# SCH_chris-dual-hd-connector-v3_2021-12-0.net
KiCad netlist of a schematic drawn in EasyEDA
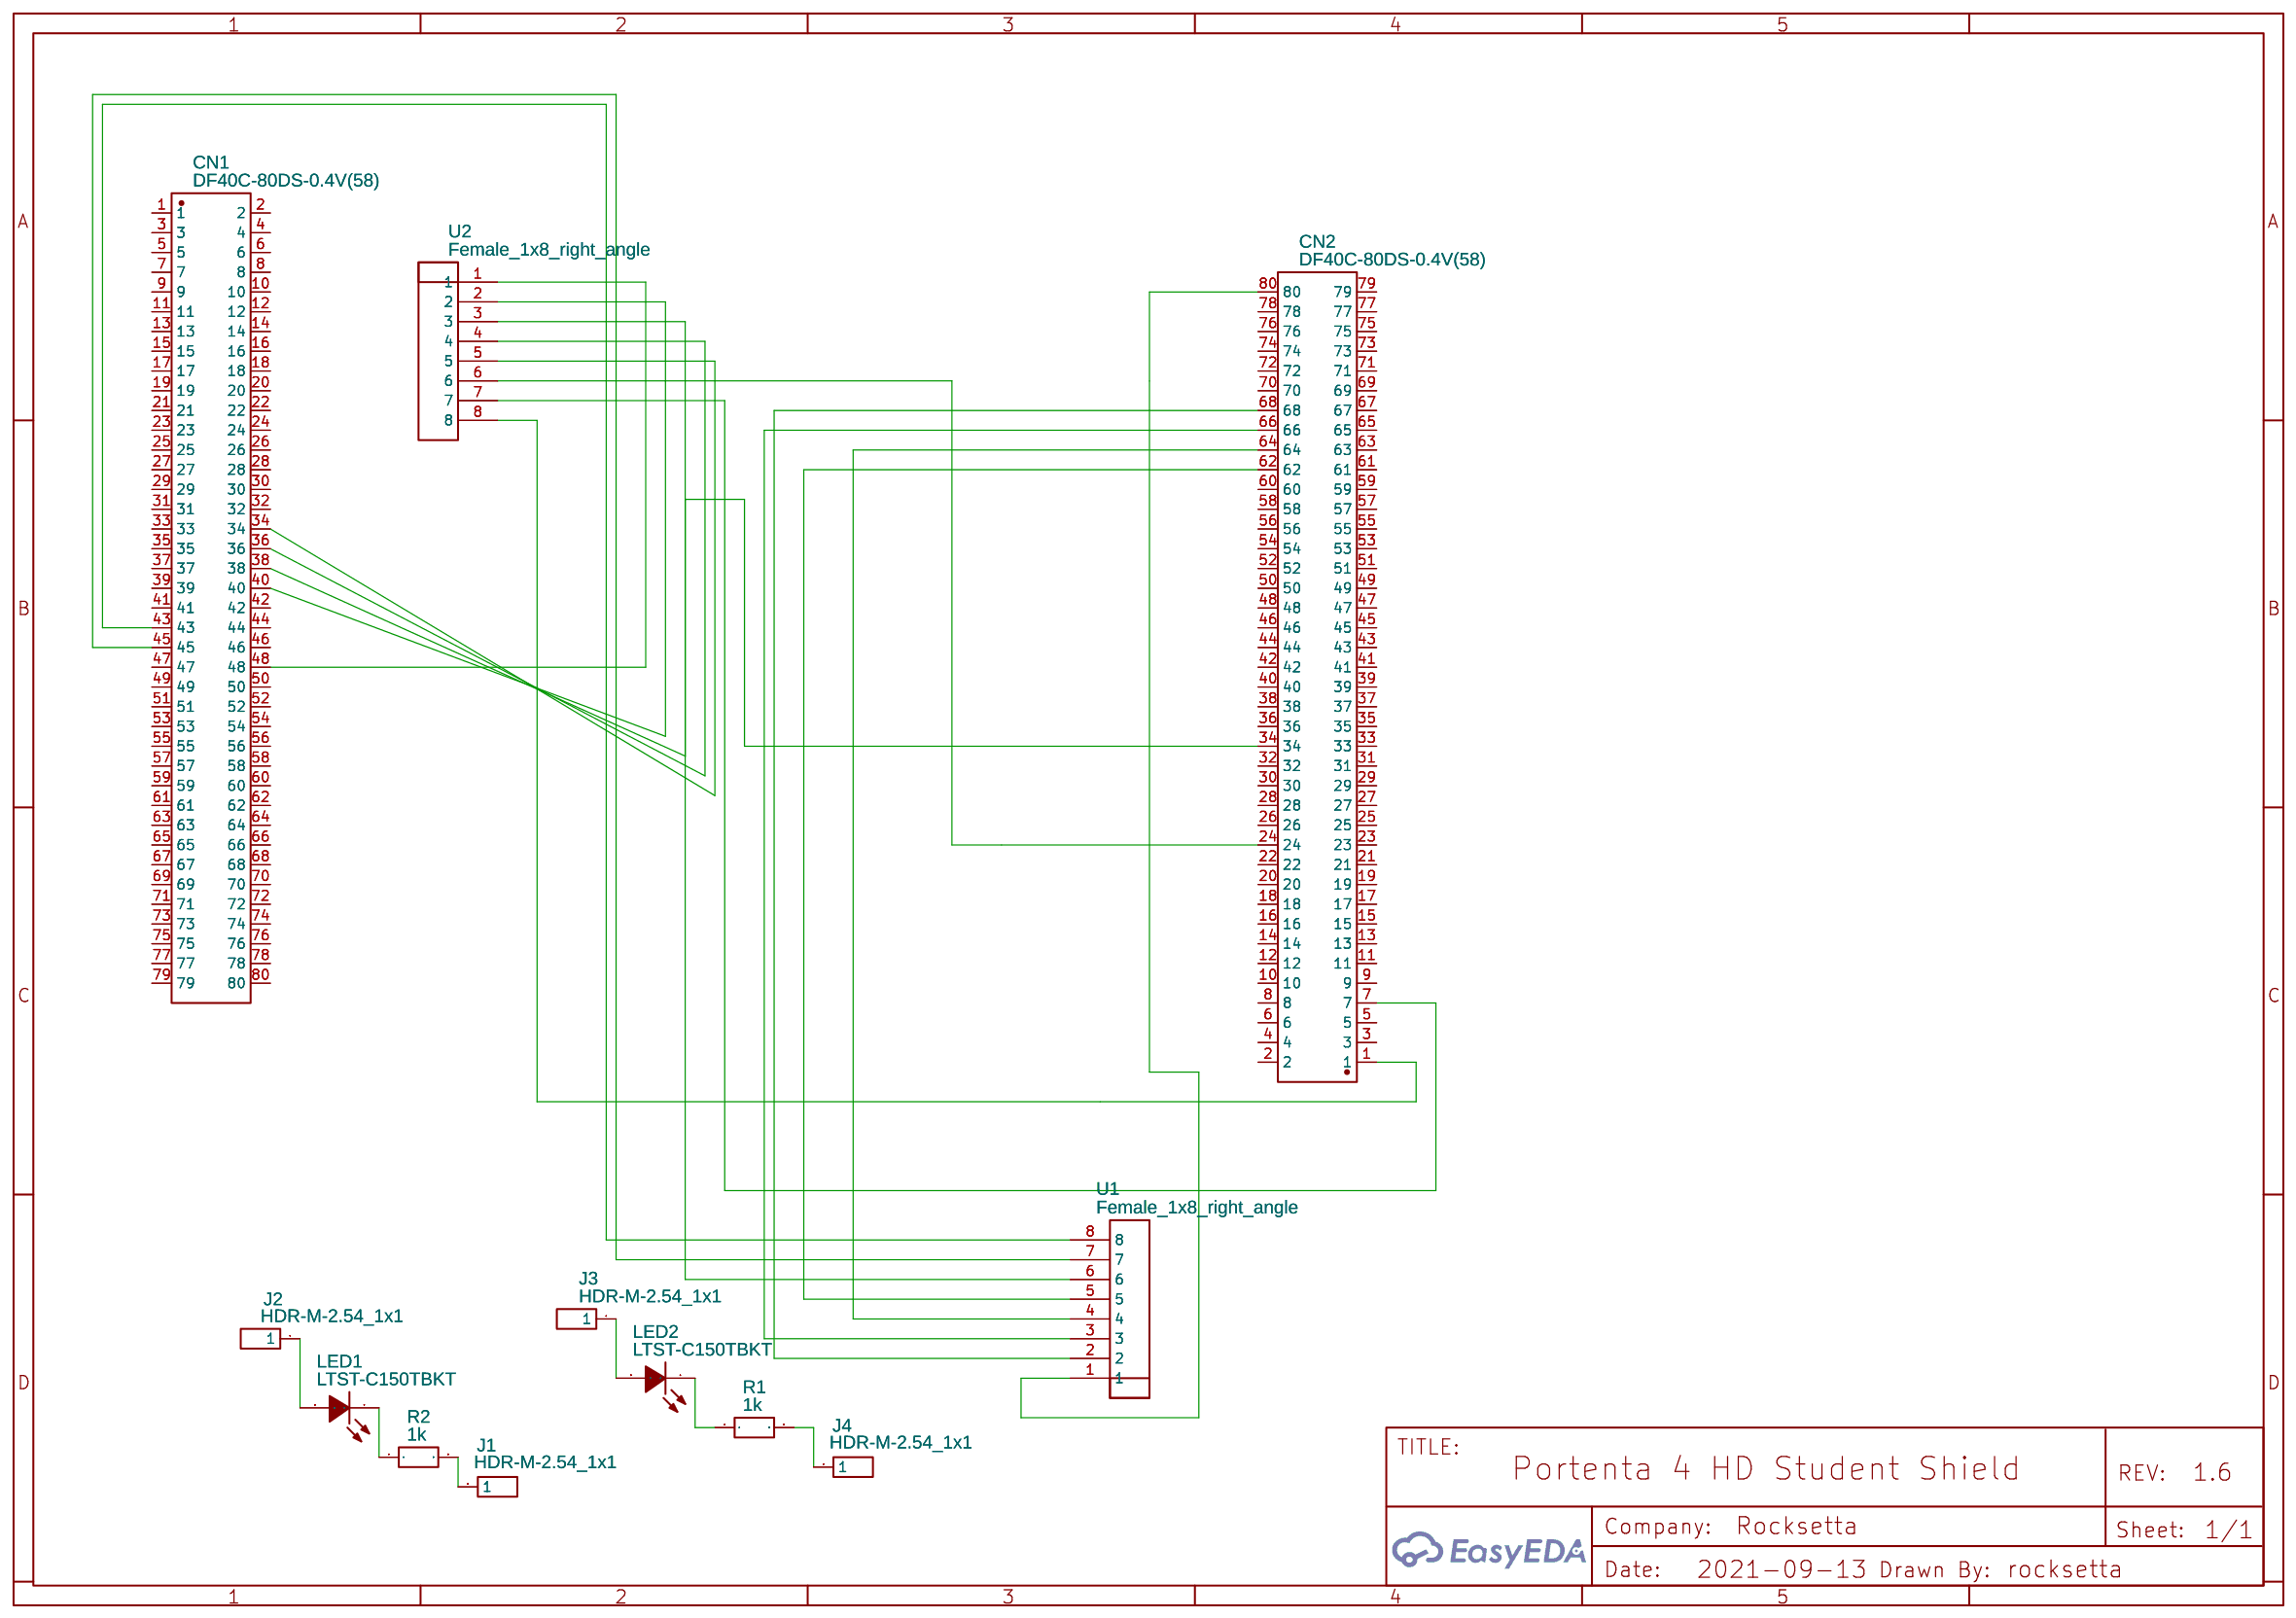
[diagram p0: schematic sheet]

(export (version "E")
  (design (tool "Eeschema 10.0.6"))
  (components
    (comp (ref "CN1")
      (value "DF40C-80DS-0.4V(58)")
      (fields (field (name "BOM_Supplier Part") "C597941"))
      (libsource (lib "") (part "DF40C-80DS-0.4V(58)_1"))
    )
    (comp (ref "CN2")
      (value "DF40C-80DS-0.4V(58)")
      (fields (field (name "BOM_Supplier Part") "C597941"))
      (libsource (lib "") (part "DF40C-80DS-0.4V(58)"))
    )
    (comp (ref "J1")
      (value "HDR-M-2.54_1x1")
      (fields (field (name "BOM_Supplier Part") "C81276"))
      (libsource (lib "") (part "HDR-M-2.54_1x1_1"))
    )
    (comp (ref "J2")
      (value "HDR-M-2.54_1x1")
      (fields (field (name "BOM_Supplier Part") "C81276"))
      (libsource (lib "") (part "HDR-M-2.54_1x1"))
    )
    (comp (ref "J3")
      (value "HDR-M-2.54_1x1")
      (fields (field (name "BOM_Supplier Part") "C81276"))
      (libsource (lib "") (part "HDR-M-2.54_1x1"))
    )
    (comp (ref "J4")
      (value "HDR-M-2.54_1x1")
      (fields (field (name "BOM_Supplier Part") "C81276"))
      (libsource (lib "") (part "HDR-M-2.54_1x1_1"))
    )
    (comp (ref "LED1")
      (value "LTST-C150TBKT")
      (fields (field (name "BOM_Supplier Part") "C125088"))
      (libsource (lib "") (part "LTST-C150TBKT"))
    )
    (comp (ref "LED2")
      (value "LTST-C150TBKT")
      (fields (field (name "BOM_Supplier Part") "C125088"))
      (libsource (lib "") (part "LTST-C150TBKT"))
    )
    (comp (ref "R1") (value "1k") (libsource (lib "") (part "R_0805_EU")))
    (comp (ref "R2") (value "1k") (libsource (lib "") (part "R_0805_EU")))
    (comp (ref "U1")
      (value "Female_1x8_right_angle")
      (fields
        (field (name "BOM_Manufacturer Part") "PPPC081LGBN-RC")
        (field (name "BOM_Supplier Part") "S5483-ND")
      )
      (libsource (lib "") (part "Female_1x8_right_angle"))
    )
    (comp (ref "U2")
      (value "Female_1x8_right_angle")
      (fields
        (field (name "BOM_Manufacturer Part") "PPPC081LGBN-RC")
        (field (name "BOM_Supplier Part") "S5483-ND")
      )
      (libsource (lib "") (part "Female_1x8_right_angle_1"))
    )
  )
  (nets
    (net (code "1") (name "Net-(CN1-Pad34)") (class "Default")
      (node (ref "CN1") (pin "34") (pinfunction "34_34") (pintype "unspecified"))
      (node (ref "U2") (pin "5") (pinfunction "5_5") (pintype "unspecified"))
    )
    (net (code "2") (name "Net-(CN1-Pad36)") (class "Default")
      (node (ref "CN1") (pin "36") (pinfunction "36_36") (pintype "unspecified"))
      (node (ref "U2") (pin "4") (pinfunction "4_4") (pintype "unspecified"))
    )
    (net (code "3") (name "Net-(CN1-Pad38)") (class "Default")
      (node (ref "CN1") (pin "38") (pinfunction "38_38") (pintype "unspecified"))
      (node (ref "U2") (pin "3") (pinfunction "3_3") (pintype "unspecified"))
    )
    (net (code "4") (name "Net-(CN1-Pad40)") (class "Default")
      (node (ref "CN1") (pin "40") (pinfunction "40_40") (pintype "unspecified"))
      (node (ref "U2") (pin "2") (pinfunction "2_2") (pintype "unspecified"))
    )
    (net (code "5") (name "Net-(CN1-Pad43)") (class "Default")
      (node (ref "CN1") (pin "43") (pinfunction "43_43") (pintype "unspecified"))
      (node (ref "U1") (pin "8") (pinfunction "8_8") (pintype "unspecified"))
    )
    (net (code "6") (name "Net-(CN1-Pad45)") (class "Default")
      (node (ref "CN1") (pin "45") (pinfunction "45_45") (pintype "unspecified"))
      (node (ref "U1") (pin "7") (pinfunction "7_7") (pintype "unspecified"))
    )
    (net (code "7") (name "Net-(CN1-Pad48)") (class "Default")
      (node (ref "CN1") (pin "48") (pinfunction "48_48") (pintype "unspecified"))
      (node (ref "U2") (pin "1") (pinfunction "1_1") (pintype "unspecified"))
    )
    (net (code "8") (name "Net-(CN2-Pad1)") (class "Default")
      (node (ref "CN2") (pin "1") (pinfunction "1_1") (pintype "unspecified"))
      (node (ref "U2") (pin "8") (pinfunction "8_8") (pintype "unspecified"))
    )
    (net (code "9") (name "Net-(CN2-Pad7)") (class "Default")
      (node (ref "CN2") (pin "7") (pinfunction "7_7") (pintype "unspecified"))
      (node (ref "U2") (pin "7") (pinfunction "7_7") (pintype "unspecified"))
    )
    (net (code "10") (name "Net-(CN2-Pad24)") (class "Default")
      (node (ref "CN2") (pin "24") (pinfunction "24_24") (pintype "unspecified"))
      (node (ref "U2") (pin "6") (pinfunction "6_6") (pintype "unspecified"))
    )
    (net (code "11") (name "Net-(CN2-Pad34)") (class "Default")
      (node (ref "CN2") (pin "34") (pinfunction "34_34") (pintype "unspecified"))
      (node (ref "U1") (pin "6") (pinfunction "6_6") (pintype "unspecified"))
    )
    (net (code "12") (name "Net-(CN2-Pad62)") (class "Default")
      (node (ref "CN2") (pin "62") (pinfunction "62_62") (pintype "unspecified"))
      (node (ref "U1") (pin "5") (pinfunction "5_5") (pintype "unspecified"))
    )
    (net (code "13") (name "Net-(CN2-Pad64)") (class "Default")
      (node (ref "CN2") (pin "64") (pinfunction "64_64") (pintype "unspecified"))
      (node (ref "U1") (pin "4") (pinfunction "4_4") (pintype "unspecified"))
    )
    (net (code "14") (name "Net-(CN2-Pad66)") (class "Default")
      (node (ref "CN2") (pin "66") (pinfunction "66_66") (pintype "unspecified"))
      (node (ref "U1") (pin "3") (pinfunction "3_3") (pintype "unspecified"))
    )
    (net (code "15") (name "Net-(CN2-Pad68)") (class "Default")
      (node (ref "CN2") (pin "68") (pinfunction "68_68") (pintype "unspecified"))
      (node (ref "U1") (pin "2") (pinfunction "2_2") (pintype "unspecified"))
    )
    (net (code "16") (name "Net-(CN2-Pad80)") (class "Default")
      (node (ref "CN2") (pin "80") (pinfunction "80_80") (pintype "unspecified"))
      (node (ref "U1") (pin "1") (pinfunction "1_1") (pintype "unspecified"))
    )
    (net (code "17") (name "Net-(J1-Pad1)") (class "Default")
      (node (ref "J1") (pin "1") (pinfunction "1_1") (pintype "input"))
      (node (ref "R2") (pin "2") (pinfunction "2_2") (pintype "unspecified"))
    )
    (net (code "18") (name "Net-(J4-Pad1)") (class "Default")
      (node (ref "J4") (pin "1") (pinfunction "1_1") (pintype "input"))
      (node (ref "R1") (pin "2") (pinfunction "2_2") (pintype "unspecified"))
    )
    (net (code "19") (name "Net-(LED1-A)") (class "Default")
      (node (ref "J2") (pin "1") (pinfunction "1_1") (pintype "input"))
      (node (ref "LED1") (pin "2") (pinfunction "A_2") (pintype "unspecified"))
    )
    (net (code "20") (name "Net-(LED1-K)") (class "Default")
      (node (ref "LED1") (pin "1") (pinfunction "K_1") (pintype "unspecified"))
      (node (ref "R2") (pin "1") (pinfunction "1_1") (pintype "unspecified"))
    )
    (net (code "21") (name "Net-(LED2-A)") (class "Default")
      (node (ref "J3") (pin "1") (pinfunction "1_1") (pintype "input"))
      (node (ref "LED2") (pin "2") (pinfunction "A_2") (pintype "unspecified"))
    )
    (net (code "22") (name "Net-(LED2-K)") (class "Default")
      (node (ref "LED2") (pin "1") (pinfunction "K_1") (pintype "unspecified"))
      (node (ref "R1") (pin "1") (pinfunction "1_1") (pintype "unspecified"))
    )
    (net (code "23") (name "unconnected-(CN1-Pad1)") (class "Default")
      (node (ref "CN1") (pin "1") (pinfunction "1_1") (pintype "unspecified"))
    )
    (net (code "24") (name "unconnected-(CN1-Pad2)") (class "Default")
      (node (ref "CN1") (pin "2") (pinfunction "2_2") (pintype "unspecified"))
    )
    (net (code "25") (name "unconnected-(CN1-Pad3)") (class "Default")
      (node (ref "CN1") (pin "3") (pinfunction "3_3") (pintype "unspecified"))
    )
    (net (code "26") (name "unconnected-(CN1-Pad4)") (class "Default")
      (node (ref "CN1") (pin "4") (pinfunction "4_4") (pintype "unspecified"))
    )
    (net (code "27") (name "unconnected-(CN1-Pad5)") (class "Default")
      (node (ref "CN1") (pin "5") (pinfunction "5_5") (pintype "unspecified"))
    )
    (net (code "28") (name "unconnected-(CN1-Pad6)") (class "Default")
      (node (ref "CN1") (pin "6") (pinfunction "6_6") (pintype "unspecified"))
    )
    (net (code "29") (name "unconnected-(CN1-Pad7)") (class "Default")
      (node (ref "CN1") (pin "7") (pinfunction "7_7") (pintype "unspecified"))
    )
    (net (code "30") (name "unconnected-(CN1-Pad8)") (class "Default")
      (node (ref "CN1") (pin "8") (pinfunction "8_8") (pintype "unspecified"))
    )
    (net (code "31") (name "unconnected-(CN1-Pad9)") (class "Default")
      (node (ref "CN1") (pin "9") (pinfunction "9_9") (pintype "unspecified"))
    )
    (net (code "32") (name "unconnected-(CN1-Pad10)") (class "Default")
      (node (ref "CN1") (pin "10") (pinfunction "10_10") (pintype "unspecified"))
    )
    (net (code "33") (name "unconnected-(CN1-Pad11)") (class "Default")
      (node (ref "CN1") (pin "11") (pinfunction "11_11") (pintype "unspecified"))
    )
    (net (code "34") (name "unconnected-(CN1-Pad12)") (class "Default")
      (node (ref "CN1") (pin "12") (pinfunction "12_12") (pintype "unspecified"))
    )
    (net (code "35") (name "unconnected-(CN1-Pad13)") (class "Default")
      (node (ref "CN1") (pin "13") (pinfunction "13_13") (pintype "unspecified"))
    )
    (net (code "36") (name "unconnected-(CN1-Pad14)") (class "Default")
      (node (ref "CN1") (pin "14") (pinfunction "14_14") (pintype "unspecified"))
    )
    (net (code "37") (name "unconnected-(CN1-Pad15)") (class "Default")
      (node (ref "CN1") (pin "15") (pinfunction "15_15") (pintype "unspecified"))
    )
    (net (code "38") (name "unconnected-(CN1-Pad16)") (class "Default")
      (node (ref "CN1") (pin "16") (pinfunction "16_16") (pintype "unspecified"))
    )
    (net (code "39") (name "unconnected-(CN1-Pad17)") (class "Default")
      (node (ref "CN1") (pin "17") (pinfunction "17_17") (pintype "unspecified"))
    )
    (net (code "40") (name "unconnected-(CN1-Pad18)") (class "Default")
      (node (ref "CN1") (pin "18") (pinfunction "18_18") (pintype "unspecified"))
    )
    (net (code "41") (name "unconnected-(CN1-Pad19)") (class "Default")
      (node (ref "CN1") (pin "19") (pinfunction "19_19") (pintype "unspecified"))
    )
    (net (code "42") (name "unconnected-(CN1-Pad20)") (class "Default")
      (node (ref "CN1") (pin "20") (pinfunction "20_20") (pintype "unspecified"))
    )
    (net (code "43") (name "unconnected-(CN1-Pad21)") (class "Default")
      (node (ref "CN1") (pin "21") (pinfunction "21_21") (pintype "unspecified"))
    )
    (net (code "44") (name "unconnected-(CN1-Pad22)") (class "Default")
      (node (ref "CN1") (pin "22") (pinfunction "22_22") (pintype "unspecified"))
    )
    (net (code "45") (name "unconnected-(CN1-Pad23)") (class "Default")
      (node (ref "CN1") (pin "23") (pinfunction "23_23") (pintype "unspecified"))
    )
    (net (code "46") (name "unconnected-(CN1-Pad24)") (class "Default")
      (node (ref "CN1") (pin "24") (pinfunction "24_24") (pintype "unspecified"))
    )
    (net (code "47") (name "unconnected-(CN1-Pad25)") (class "Default")
      (node (ref "CN1") (pin "25") (pinfunction "25_25") (pintype "unspecified"))
    )
    (net (code "48") (name "unconnected-(CN1-Pad26)") (class "Default")
      (node (ref "CN1") (pin "26") (pinfunction "26_26") (pintype "unspecified"))
    )
    (net (code "49") (name "unconnected-(CN1-Pad27)") (class "Default")
      (node (ref "CN1") (pin "27") (pinfunction "27_27") (pintype "unspecified"))
    )
    (net (code "50") (name "unconnected-(CN1-Pad28)") (class "Default")
      (node (ref "CN1") (pin "28") (pinfunction "28_28") (pintype "unspecified"))
    )
    (net (code "51") (name "unconnected-(CN1-Pad29)") (class "Default")
      (node (ref "CN1") (pin "29") (pinfunction "29_29") (pintype "unspecified"))
    )
    (net (code "52") (name "unconnected-(CN1-Pad30)") (class "Default")
      (node (ref "CN1") (pin "30") (pinfunction "30_30") (pintype "unspecified"))
    )
    (net (code "53") (name "unconnected-(CN1-Pad31)") (class "Default")
      (node (ref "CN1") (pin "31") (pinfunction "31_31") (pintype "unspecified"))
    )
    (net (code "54") (name "unconnected-(CN1-Pad32)") (class "Default")
      (node (ref "CN1") (pin "32") (pinfunction "32_32") (pintype "unspecified"))
    )
    (net (code "55") (name "unconnected-(CN1-Pad33)") (class "Default")
      (node (ref "CN1") (pin "33") (pinfunction "33_33") (pintype "unspecified"))
    )
    (net (code "56") (name "unconnected-(CN1-Pad35)") (class "Default")
      (node (ref "CN1") (pin "35") (pinfunction "35_35") (pintype "unspecified"))
    )
    (net (code "57") (name "unconnected-(CN1-Pad37)") (class "Default")
      (node (ref "CN1") (pin "37") (pinfunction "37_37") (pintype "unspecified"))
    )
    (net (code "58") (name "unconnected-(CN1-Pad39)") (class "Default")
      (node (ref "CN1") (pin "39") (pinfunction "39_39") (pintype "unspecified"))
    )
    (net (code "59") (name "unconnected-(CN1-Pad41)") (class "Default")
      (node (ref "CN1") (pin "41") (pinfunction "41_41") (pintype "unspecified"))
    )
    (net (code "60") (name "unconnected-(CN1-Pad42)") (class "Default")
      (node (ref "CN1") (pin "42") (pinfunction "42_42") (pintype "unspecified"))
    )
    (net (code "61") (name "unconnected-(CN1-Pad44)") (class "Default")
      (node (ref "CN1") (pin "44") (pinfunction "44_44") (pintype "unspecified"))
    )
    (net (code "62") (name "unconnected-(CN1-Pad46)") (class "Default")
      (node (ref "CN1") (pin "46") (pinfunction "46_46") (pintype "unspecified"))
    )
    (net (code "63") (name "unconnected-(CN1-Pad47)") (class "Default")
      (node (ref "CN1") (pin "47") (pinfunction "47_47") (pintype "unspecified"))
    )
    (net (code "64") (name "unconnected-(CN1-Pad49)") (class "Default")
      (node (ref "CN1") (pin "49") (pinfunction "49_49") (pintype "unspecified"))
    )
    (net (code "65") (name "unconnected-(CN1-Pad50)") (class "Default")
      (node (ref "CN1") (pin "50") (pinfunction "50_50") (pintype "unspecified"))
    )
    (net (code "66") (name "unconnected-(CN1-Pad51)") (class "Default")
      (node (ref "CN1") (pin "51") (pinfunction "51_51") (pintype "unspecified"))
    )
    (net (code "67") (name "unconnected-(CN1-Pad52)") (class "Default")
      (node (ref "CN1") (pin "52") (pinfunction "52_52") (pintype "unspecified"))
    )
    (net (code "68") (name "unconnected-(CN1-Pad53)") (class "Default")
      (node (ref "CN1") (pin "53") (pinfunction "53_53") (pintype "unspecified"))
    )
    (net (code "69") (name "unconnected-(CN1-Pad54)") (class "Default")
      (node (ref "CN1") (pin "54") (pinfunction "54_54") (pintype "unspecified"))
    )
    (net (code "70") (name "unconnected-(CN1-Pad55)") (class "Default")
      (node (ref "CN1") (pin "55") (pinfunction "55_55") (pintype "unspecified"))
    )
    (net (code "71") (name "unconnected-(CN1-Pad56)") (class "Default")
      (node (ref "CN1") (pin "56") (pinfunction "56_56") (pintype "unspecified"))
    )
    (net (code "72") (name "unconnected-(CN1-Pad57)") (class "Default")
      (node (ref "CN1") (pin "57") (pinfunction "57_57") (pintype "unspecified"))
    )
    (net (code "73") (name "unconnected-(CN1-Pad58)") (class "Default")
      (node (ref "CN1") (pin "58") (pinfunction "58_58") (pintype "unspecified"))
    )
    (net (code "74") (name "unconnected-(CN1-Pad59)") (class "Default")
      (node (ref "CN1") (pin "59") (pinfunction "59_59") (pintype "unspecified"))
    )
    (net (code "75") (name "unconnected-(CN1-Pad60)") (class "Default")
      (node (ref "CN1") (pin "60") (pinfunction "60_60") (pintype "unspecified"))
    )
    (net (code "76") (name "unconnected-(CN1-Pad61)") (class "Default")
      (node (ref "CN1") (pin "61") (pinfunction "61_61") (pintype "unspecified"))
    )
    (net (code "77") (name "unconnected-(CN1-Pad62)") (class "Default")
      (node (ref "CN1") (pin "62") (pinfunction "62_62") (pintype "unspecified"))
    )
    (net (code "78") (name "unconnected-(CN1-Pad63)") (class "Default")
      (node (ref "CN1") (pin "63") (pinfunction "63_63") (pintype "unspecified"))
    )
    (net (code "79") (name "unconnected-(CN1-Pad64)") (class "Default")
      (node (ref "CN1") (pin "64") (pinfunction "64_64") (pintype "unspecified"))
    )
    (net (code "80") (name "unconnected-(CN1-Pad65)") (class "Default")
      (node (ref "CN1") (pin "65") (pinfunction "65_65") (pintype "unspecified"))
    )
    (net (code "81") (name "unconnected-(CN1-Pad66)") (class "Default")
      (node (ref "CN1") (pin "66") (pinfunction "66_66") (pintype "unspecified"))
    )
    (net (code "82") (name "unconnected-(CN1-Pad67)") (class "Default")
      (node (ref "CN1") (pin "67") (pinfunction "67_67") (pintype "unspecified"))
    )
    (net (code "83") (name "unconnected-(CN1-Pad68)") (class "Default")
      (node (ref "CN1") (pin "68") (pinfunction "68_68") (pintype "unspecified"))
    )
    (net (code "84") (name "unconnected-(CN1-Pad69)") (class "Default")
      (node (ref "CN1") (pin "69") (pinfunction "69_69") (pintype "unspecified"))
    )
    (net (code "85") (name "unconnected-(CN1-Pad70)") (class "Default")
      (node (ref "CN1") (pin "70") (pinfunction "70_70") (pintype "unspecified"))
    )
    (net (code "86") (name "unconnected-(CN1-Pad71)") (class "Default")
      (node (ref "CN1") (pin "71") (pinfunction "71_71") (pintype "unspecified"))
    )
    (net (code "87") (name "unconnected-(CN1-Pad72)") (class "Default")
      (node (ref "CN1") (pin "72") (pinfunction "72_72") (pintype "unspecified"))
    )
    (net (code "88") (name "unconnected-(CN1-Pad73)") (class "Default")
      (node (ref "CN1") (pin "73") (pinfunction "73_73") (pintype "unspecified"))
    )
    (net (code "89") (name "unconnected-(CN1-Pad74)") (class "Default")
      (node (ref "CN1") (pin "74") (pinfunction "74_74") (pintype "unspecified"))
    )
    (net (code "90") (name "unconnected-(CN1-Pad75)") (class "Default")
      (node (ref "CN1") (pin "75") (pinfunction "75_75") (pintype "unspecified"))
    )
    (net (code "91") (name "unconnected-(CN1-Pad76)") (class "Default")
      (node (ref "CN1") (pin "76") (pinfunction "76_76") (pintype "unspecified"))
    )
    (net (code "92") (name "unconnected-(CN1-Pad77)") (class "Default")
      (node (ref "CN1") (pin "77") (pinfunction "77_77") (pintype "unspecified"))
    )
    (net (code "93") (name "unconnected-(CN1-Pad78)") (class "Default")
      (node (ref "CN1") (pin "78") (pinfunction "78_78") (pintype "unspecified"))
    )
    (net (code "94") (name "unconnected-(CN1-Pad79)") (class "Default")
      (node (ref "CN1") (pin "79") (pinfunction "79_79") (pintype "unspecified"))
    )
    (net (code "95") (name "unconnected-(CN1-Pad80)") (class "Default")
      (node (ref "CN1") (pin "80") (pinfunction "80_80") (pintype "unspecified"))
    )
    (net (code "96") (name "unconnected-(CN2-Pad2)") (class "Default")
      (node (ref "CN2") (pin "2") (pinfunction "2_2") (pintype "unspecified"))
    )
    (net (code "97") (name "unconnected-(CN2-Pad3)") (class "Default")
      (node (ref "CN2") (pin "3") (pinfunction "3_3") (pintype "unspecified"))
    )
    (net (code "98") (name "unconnected-(CN2-Pad4)") (class "Default")
      (node (ref "CN2") (pin "4") (pinfunction "4_4") (pintype "unspecified"))
    )
    (net (code "99") (name "unconnected-(CN2-Pad5)") (class "Default")
      (node (ref "CN2") (pin "5") (pinfunction "5_5") (pintype "unspecified"))
    )
    (net (code "100") (name "unconnected-(CN2-Pad6)") (class "Default")
      (node (ref "CN2") (pin "6") (pinfunction "6_6") (pintype "unspecified"))
    )
    (net (code "101") (name "unconnected-(CN2-Pad8)") (class "Default")
      (node (ref "CN2") (pin "8") (pinfunction "8_8") (pintype "unspecified"))
    )
    (net (code "102") (name "unconnected-(CN2-Pad9)") (class "Default")
      (node (ref "CN2") (pin "9") (pinfunction "9_9") (pintype "unspecified"))
    )
    (net (code "103") (name "unconnected-(CN2-Pad10)") (class "Default")
      (node (ref "CN2") (pin "10") (pinfunction "10_10") (pintype "unspecified"))
    )
    (net (code "104") (name "unconnected-(CN2-Pad11)") (class "Default")
      (node (ref "CN2") (pin "11") (pinfunction "11_11") (pintype "unspecified"))
    )
    (net (code "105") (name "unconnected-(CN2-Pad12)") (class "Default")
      (node (ref "CN2") (pin "12") (pinfunction "12_12") (pintype "unspecified"))
    )
    (net (code "106") (name "unconnected-(CN2-Pad13)") (class "Default")
      (node (ref "CN2") (pin "13") (pinfunction "13_13") (pintype "unspecified"))
    )
    (net (code "107") (name "unconnected-(CN2-Pad14)") (class "Default")
      (node (ref "CN2") (pin "14") (pinfunction "14_14") (pintype "unspecified"))
    )
    (net (code "108") (name "unconnected-(CN2-Pad15)") (class "Default")
      (node (ref "CN2") (pin "15") (pinfunction "15_15") (pintype "unspecified"))
    )
    (net (code "109") (name "unconnected-(CN2-Pad16)") (class "Default")
      (node (ref "CN2") (pin "16") (pinfunction "16_16") (pintype "unspecified"))
    )
    (net (code "110") (name "unconnected-(CN2-Pad17)") (class "Default")
      (node (ref "CN2") (pin "17") (pinfunction "17_17") (pintype "unspecified"))
    )
    (net (code "111") (name "unconnected-(CN2-Pad18)") (class "Default")
      (node (ref "CN2") (pin "18") (pinfunction "18_18") (pintype "unspecified"))
    )
    (net (code "112") (name "unconnected-(CN2-Pad19)") (class "Default")
      (node (ref "CN2") (pin "19") (pinfunction "19_19") (pintype "unspecified"))
    )
    (net (code "113") (name "unconnected-(CN2-Pad20)") (class "Default")
      (node (ref "CN2") (pin "20") (pinfunction "20_20") (pintype "unspecified"))
    )
    (net (code "114") (name "unconnected-(CN2-Pad21)") (class "Default")
      (node (ref "CN2") (pin "21") (pinfunction "21_21") (pintype "unspecified"))
    )
    (net (code "115") (name "unconnected-(CN2-Pad22)") (class "Default")
      (node (ref "CN2") (pin "22") (pinfunction "22_22") (pintype "unspecified"))
    )
    (net (code "116") (name "unconnected-(CN2-Pad23)") (class "Default")
      (node (ref "CN2") (pin "23") (pinfunction "23_23") (pintype "unspecified"))
    )
    (net (code "117") (name "unconnected-(CN2-Pad25)") (class "Default")
      (node (ref "CN2") (pin "25") (pinfunction "25_25") (pintype "unspecified"))
    )
    (net (code "118") (name "unconnected-(CN2-Pad26)") (class "Default")
      (node (ref "CN2") (pin "26") (pinfunction "26_26") (pintype "unspecified"))
    )
    (net (code "119") (name "unconnected-(CN2-Pad27)") (class "Default")
      (node (ref "CN2") (pin "27") (pinfunction "27_27") (pintype "unspecified"))
    )
    (net (code "120") (name "unconnected-(CN2-Pad28)") (class "Default")
      (node (ref "CN2") (pin "28") (pinfunction "28_28") (pintype "unspecified"))
    )
    (net (code "121") (name "unconnected-(CN2-Pad29)") (class "Default")
      (node (ref "CN2") (pin "29") (pinfunction "29_29") (pintype "unspecified"))
    )
    (net (code "122") (name "unconnected-(CN2-Pad30)") (class "Default")
      (node (ref "CN2") (pin "30") (pinfunction "30_30") (pintype "unspecified"))
    )
    (net (code "123") (name "unconnected-(CN2-Pad31)") (class "Default")
      (node (ref "CN2") (pin "31") (pinfunction "31_31") (pintype "unspecified"))
    )
    (net (code "124") (name "unconnected-(CN2-Pad32)") (class "Default")
      (node (ref "CN2") (pin "32") (pinfunction "32_32") (pintype "unspecified"))
    )
    (net (code "125") (name "unconnected-(CN2-Pad33)") (class "Default")
      (node (ref "CN2") (pin "33") (pinfunction "33_33") (pintype "unspecified"))
    )
    (net (code "126") (name "unconnected-(CN2-Pad35)") (class "Default")
      (node (ref "CN2") (pin "35") (pinfunction "35_35") (pintype "unspecified"))
    )
    (net (code "127") (name "unconnected-(CN2-Pad36)") (class "Default")
      (node (ref "CN2") (pin "36") (pinfunction "36_36") (pintype "unspecified"))
    )
    (net (code "128") (name "unconnected-(CN2-Pad37)") (class "Default")
      (node (ref "CN2") (pin "37") (pinfunction "37_37") (pintype "unspecified"))
    )
    (net (code "129") (name "unconnected-(CN2-Pad38)") (class "Default")
      (node (ref "CN2") (pin "38") (pinfunction "38_38") (pintype "unspecified"))
    )
    (net (code "130") (name "unconnected-(CN2-Pad39)") (class "Default")
      (node (ref "CN2") (pin "39") (pinfunction "39_39") (pintype "unspecified"))
    )
    (net (code "131") (name "unconnected-(CN2-Pad40)") (class "Default")
      (node (ref "CN2") (pin "40") (pinfunction "40_40") (pintype "unspecified"))
    )
    (net (code "132") (name "unconnected-(CN2-Pad41)") (class "Default")
      (node (ref "CN2") (pin "41") (pinfunction "41_41") (pintype "unspecified"))
    )
    (net (code "133") (name "unconnected-(CN2-Pad42)") (class "Default")
      (node (ref "CN2") (pin "42") (pinfunction "42_42") (pintype "unspecified"))
    )
    (net (code "134") (name "unconnected-(CN2-Pad43)") (class "Default")
      (node (ref "CN2") (pin "43") (pinfunction "43_43") (pintype "unspecified"))
    )
    (net (code "135") (name "unconnected-(CN2-Pad44)") (class "Default")
      (node (ref "CN2") (pin "44") (pinfunction "44_44") (pintype "unspecified"))
    )
    (net (code "136") (name "unconnected-(CN2-Pad45)") (class "Default")
      (node (ref "CN2") (pin "45") (pinfunction "45_45") (pintype "unspecified"))
    )
    (net (code "137") (name "unconnected-(CN2-Pad46)") (class "Default")
      (node (ref "CN2") (pin "46") (pinfunction "46_46") (pintype "unspecified"))
    )
    (net (code "138") (name "unconnected-(CN2-Pad47)") (class "Default")
      (node (ref "CN2") (pin "47") (pinfunction "47_47") (pintype "unspecified"))
    )
    (net (code "139") (name "unconnected-(CN2-Pad48)") (class "Default")
      (node (ref "CN2") (pin "48") (pinfunction "48_48") (pintype "unspecified"))
    )
    (net (code "140") (name "unconnected-(CN2-Pad49)") (class "Default")
      (node (ref "CN2") (pin "49") (pinfunction "49_49") (pintype "unspecified"))
    )
    (net (code "141") (name "unconnected-(CN2-Pad50)") (class "Default")
      (node (ref "CN2") (pin "50") (pinfunction "50_50") (pintype "unspecified"))
    )
    (net (code "142") (name "unconnected-(CN2-Pad51)") (class "Default")
      (node (ref "CN2") (pin "51") (pinfunction "51_51") (pintype "unspecified"))
    )
    (net (code "143") (name "unconnected-(CN2-Pad52)") (class "Default")
      (node (ref "CN2") (pin "52") (pinfunction "52_52") (pintype "unspecified"))
    )
    (net (code "144") (name "unconnected-(CN2-Pad53)") (class "Default")
      (node (ref "CN2") (pin "53") (pinfunction "53_53") (pintype "unspecified"))
    )
    (net (code "145") (name "unconnected-(CN2-Pad54)") (class "Default")
      (node (ref "CN2") (pin "54") (pinfunction "54_54") (pintype "unspecified"))
    )
    (net (code "146") (name "unconnected-(CN2-Pad55)") (class "Default")
      (node (ref "CN2") (pin "55") (pinfunction "55_55") (pintype "unspecified"))
    )
    (net (code "147") (name "unconnected-(CN2-Pad56)") (class "Default")
      (node (ref "CN2") (pin "56") (pinfunction "56_56") (pintype "unspecified"))
    )
    (net (code "148") (name "unconnected-(CN2-Pad57)") (class "Default")
      (node (ref "CN2") (pin "57") (pinfunction "57_57") (pintype "unspecified"))
    )
    (net (code "149") (name "unconnected-(CN2-Pad58)") (class "Default")
      (node (ref "CN2") (pin "58") (pinfunction "58_58") (pintype "unspecified"))
    )
    (net (code "150") (name "unconnected-(CN2-Pad59)") (class "Default")
      (node (ref "CN2") (pin "59") (pinfunction "59_59") (pintype "unspecified"))
    )
    (net (code "151") (name "unconnected-(CN2-Pad60)") (class "Default")
      (node (ref "CN2") (pin "60") (pinfunction "60_60") (pintype "unspecified"))
    )
    (net (code "152") (name "unconnected-(CN2-Pad61)") (class "Default")
      (node (ref "CN2") (pin "61") (pinfunction "61_61") (pintype "unspecified"))
    )
    (net (code "153") (name "unconnected-(CN2-Pad63)") (class "Default")
      (node (ref "CN2") (pin "63") (pinfunction "63_63") (pintype "unspecified"))
    )
    (net (code "154") (name "unconnected-(CN2-Pad65)") (class "Default")
      (node (ref "CN2") (pin "65") (pinfunction "65_65") (pintype "unspecified"))
    )
    (net (code "155") (name "unconnected-(CN2-Pad67)") (class "Default")
      (node (ref "CN2") (pin "67") (pinfunction "67_67") (pintype "unspecified"))
    )
    (net (code "156") (name "unconnected-(CN2-Pad69)") (class "Default")
      (node (ref "CN2") (pin "69") (pinfunction "69_69") (pintype "unspecified"))
    )
    (net (code "157") (name "unconnected-(CN2-Pad70)") (class "Default")
      (node (ref "CN2") (pin "70") (pinfunction "70_70") (pintype "unspecified"))
    )
    (net (code "158") (name "unconnected-(CN2-Pad71)") (class "Default")
      (node (ref "CN2") (pin "71") (pinfunction "71_71") (pintype "unspecified"))
    )
    (net (code "159") (name "unconnected-(CN2-Pad72)") (class "Default")
      (node (ref "CN2") (pin "72") (pinfunction "72_72") (pintype "unspecified"))
    )
    (net (code "160") (name "unconnected-(CN2-Pad73)") (class "Default")
      (node (ref "CN2") (pin "73") (pinfunction "73_73") (pintype "unspecified"))
    )
    (net (code "161") (name "unconnected-(CN2-Pad74)") (class "Default")
      (node (ref "CN2") (pin "74") (pinfunction "74_74") (pintype "unspecified"))
    )
    (net (code "162") (name "unconnected-(CN2-Pad75)") (class "Default")
      (node (ref "CN2") (pin "75") (pinfunction "75_75") (pintype "unspecified"))
    )
    (net (code "163") (name "unconnected-(CN2-Pad76)") (class "Default")
      (node (ref "CN2") (pin "76") (pinfunction "76_76") (pintype "unspecified"))
    )
    (net (code "164") (name "unconnected-(CN2-Pad77)") (class "Default")
      (node (ref "CN2") (pin "77") (pinfunction "77_77") (pintype "unspecified"))
    )
    (net (code "165") (name "unconnected-(CN2-Pad78)") (class "Default")
      (node (ref "CN2") (pin "78") (pinfunction "78_78") (pintype "unspecified"))
    )
    (net (code "166") (name "unconnected-(CN2-Pad79)") (class "Default")
      (node (ref "CN2") (pin "79") (pinfunction "79_79") (pintype "unspecified"))
    )
  )
)
